# transmisorPCB_2_1.net
KiCad netlist of a schematic drawn in EAGLE
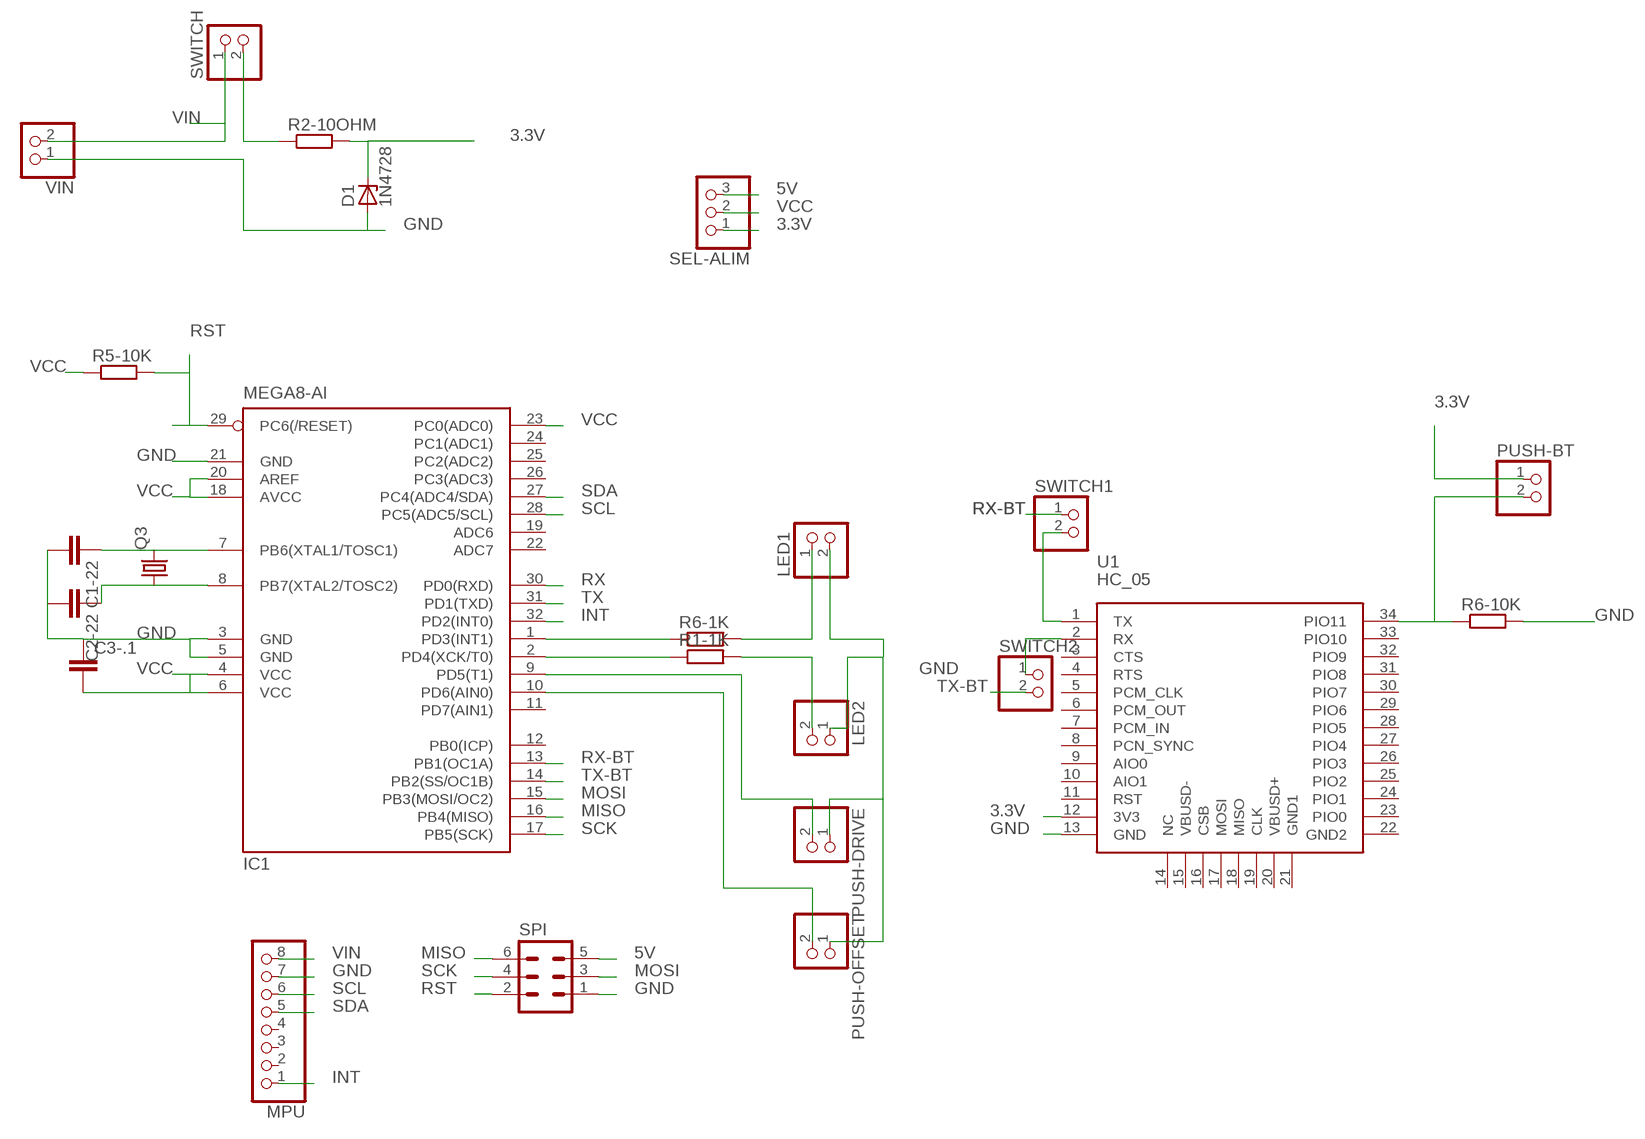
[diagram p0: schematic, sheet 1]

(export (version "E")
  (design (tool "Eeschema 10.0.6"))
  (components
    (comp (ref "C1-22")
      (value "C-EUC0402K")
      (footprint "eagle-import:C0402K")
      (libsource (lib "eagle-import") (part "C-EUC0402K"))
    )
    (comp (ref "C2-22")
      (value "C-EUC0402K")
      (footprint "eagle-import:C0402K")
      (libsource (lib "eagle-import") (part "C-EUC0402K"))
    )
    (comp (ref "C3-.1")
      (value "C-EUC0402K")
      (footprint "eagle-import:C0402K")
      (libsource (lib "eagle-import") (part "C-EUC0402K"))
    )
    (comp (ref "D1")
      (value "1N4728")
      (footprint "eagle-import:DO41Z10")
      (libsource (lib "eagle-import") (part "1N4728"))
    )
    (comp (ref "IC1")
      (value "MEGA8-AI")
      (footprint "eagle-import:TQFP32-08")
      (fields (field (name "MPN") "ATMEGA8-16AU"))
      (libsource (lib "eagle-import") (part "MEGA8-AI"))
    )
    (comp (ref "LED1")
      (value "PINHD-1X2")
      (footprint "eagle-import:1X02")
      (libsource (lib "eagle-import") (part "PINHD-1X2"))
    )
    (comp (ref "LED2")
      (value "PINHD-1X2")
      (footprint "eagle-import:1X02")
      (libsource (lib "eagle-import") (part "PINHD-1X2"))
    )
    (comp (ref "MPU")
      (value "PINHD-1X8")
      (footprint "eagle-import:1X08")
      (libsource (lib "eagle-import") (part "PINHD-1X8"))
    )
    (comp (ref "PUSH-BT")
      (value "PINHD-1X2")
      (footprint "eagle-import:1X02")
      (libsource (lib "eagle-import") (part "PINHD-1X2"))
    )
    (comp (ref "PUSH-DRIVE")
      (value "PINHD-1X2")
      (footprint "eagle-import:1X02")
      (libsource (lib "eagle-import") (part "PINHD-1X2"))
    )
    (comp (ref "PUSH-OFFSET")
      (value "PINHD-1X2")
      (footprint "eagle-import:1X02")
      (libsource (lib "eagle-import") (part "PINHD-1X2"))
    )
    (comp (ref "Q3")
      (value "CRYSTALHC49U70")
      (footprint "eagle-import:HC49U70")
      (libsource (lib "eagle-import") (part "CRYSTALHC49U70"))
    )
    (comp (ref "R1-1K")
      (value "R-EU_M1206")
      (footprint "eagle-import:M1206")
      (libsource (lib "eagle-import") (part "R-EU_M1206"))
    )
    (comp (ref "R2-10OHM")
      (value "R-EU_R2512")
      (footprint "eagle-import:R2512")
      (libsource (lib "eagle-import") (part "resistor_R-EU_R2512"))
    )
    (comp (ref "R5-10K")
      (value "R-EU_M1206")
      (footprint "eagle-import:M1206")
      (libsource (lib "eagle-import") (part "R-EU_M1206"))
    )
    (comp (ref "R6-1K")
      (value "R-EU_M1206")
      (footprint "eagle-import:M1206")
      (libsource (lib "eagle-import") (part "R-EU_M1206"))
    )
    (comp (ref "R6-10K")
      (value "R-EU_M1206")
      (footprint "eagle-import:M1206")
      (libsource (lib "eagle-import") (part "R-EU_M1206"))
    )
    (comp (ref "SEL-ALIM")
      (value "PINHD-1X3")
      (footprint "eagle-import:1X03")
      (libsource (lib "eagle-import") (part "PINHD-1X3"))
    )
    (comp (ref "SPI")
      (value "MA03-2")
      (footprint "eagle-import:MA03-2")
      (libsource (lib "eagle-import") (part "MA03-2"))
    )
    (comp (ref "SWITCH")
      (value "PINHD-1X2")
      (footprint "eagle-import:1X02")
      (libsource (lib "eagle-import") (part "PINHD-1X2"))
    )
    (comp (ref "SWITCH1")
      (value "PINHD-1X2")
      (footprint "eagle-import:1X02")
      (libsource (lib "eagle-import") (part "PINHD-1X2"))
    )
    (comp (ref "SWITCH2")
      (value "PINHD-1X2")
      (footprint "eagle-import:1X02")
      (libsource (lib "eagle-import") (part "PINHD-1X2"))
    )
    (comp (ref "U1")
      (value "HC_05")
      (footprint "eagle-import:BLUETOOTH_SMD")
      (libsource (lib "eagle-import") (part "HC_05"))
    )
    (comp (ref "VIN")
      (value "PINHD-1X2")
      (footprint "eagle-import:1X02")
      (libsource (lib "eagle-import") (part "PINHD-1X2"))
    )
  )
  (nets
    (net (code "1") (name "/3.3V") (class "Default")
      (node (ref "D1") (pin "C") (pinfunction "C_C") (pintype "passive"))
      (node (ref "PUSH-BT") (pin "1") (pinfunction "1_1") (pintype "passive"))
      (node (ref "R2-10OHM") (pin "2") (pinfunction "2_2") (pintype "passive"))
      (node (ref "SEL-ALIM") (pin "1") (pinfunction "1_1") (pintype "passive"))
      (node (ref "U1") (pin "12") (pinfunction "3V3_12") (pintype "bidirectional"))
    )
    (net (code "2") (name "/5V") (class "Default")
      (node (ref "SEL-ALIM") (pin "3") (pinfunction "3_3") (pintype "passive"))
      (node (ref "SPI") (pin "5") (pinfunction "5_5") (pintype "passive"))
    )
    (net (code "3") (name "/GND") (class "Default")
      (node (ref "C1-22") (pin "2") (pinfunction "2_2") (pintype "passive"))
      (node (ref "C2-22") (pin "2") (pinfunction "2_2") (pintype "passive"))
      (node (ref "C3-.1") (pin "1") (pinfunction "1_1") (pintype "passive"))
      (node (ref "D1") (pin "A") (pinfunction "A_A") (pintype "passive"))
      (node (ref "IC1") (pin "21") (pinfunction "GND_21") (pintype "power_in"))
      (node (ref "IC1") (pin "3") (pinfunction "GND_3") (pintype "power_in"))
      (node (ref "IC1") (pin "5") (pinfunction "GND_5") (pintype "power_in"))
      (node (ref "LED1") (pin "2") (pinfunction "2_2") (pintype "passive"))
      (node (ref "LED2") (pin "1") (pinfunction "1_1") (pintype "passive"))
      (node (ref "MPU") (pin "7") (pinfunction "7_7") (pintype "passive"))
      (node (ref "PUSH-DRIVE") (pin "1") (pinfunction "1_1") (pintype "passive"))
      (node (ref "PUSH-OFFSET") (pin "1") (pinfunction "1_1") (pintype "passive"))
      (node (ref "R6-10K") (pin "2") (pinfunction "2_2") (pintype "passive"))
      (node (ref "SPI") (pin "1") (pinfunction "1_1") (pintype "passive"))
      (node (ref "U1") (pin "13") (pinfunction "GND_13") (pintype "bidirectional"))
      (node (ref "VIN") (pin "1") (pinfunction "1_1") (pintype "passive"))
    )
    (net (code "4") (name "/INT") (class "Default")
      (node (ref "IC1") (pin "32") (pinfunction "PD2(INT0)_32") (pintype "bidirectional"))
      (node (ref "MPU") (pin "1") (pinfunction "1_1") (pintype "passive"))
    )
    (net (code "5") (name "/MISO") (class "Default")
      (node (ref "IC1") (pin "16") (pinfunction "PB4(MISO)_16") (pintype "bidirectional"))
      (node (ref "SPI") (pin "6") (pinfunction "6_6") (pintype "passive"))
    )
    (net (code "6") (name "/MOSI") (class "Default")
      (node (ref "IC1") (pin "15") (pinfunction "PB3(MOSI/OC2)_15") (pintype "bidirectional"))
      (node (ref "SPI") (pin "3") (pinfunction "3_3") (pintype "passive"))
    )
    (net (code "7") (name "/RST") (class "Default")
      (node (ref "IC1") (pin "29") (pinfunction "PC6(/RESET)_29") (pintype "bidirectional"))
      (node (ref "R5-10K") (pin "2") (pinfunction "2_2") (pintype "passive"))
      (node (ref "SPI") (pin "2") (pinfunction "2_2") (pintype "passive"))
    )
    (net (code "8") (name "/RX") (class "Default")
      (node (ref "IC1") (pin "30") (pinfunction "PD0(RXD)_30") (pintype "bidirectional"))
    )
    (net (code "9") (name "/RX-BT") (class "Default")
      (node (ref "IC1") (pin "13") (pinfunction "PB1(OC1A)_13") (pintype "bidirectional"))
      (node (ref "SWITCH1") (pin "1") (pinfunction "1_1") (pintype "passive"))
    )
    (net (code "10") (name "/SCK") (class "Default")
      (node (ref "IC1") (pin "17") (pinfunction "PB5(SCK)_17") (pintype "bidirectional"))
      (node (ref "SPI") (pin "4") (pinfunction "4_4") (pintype "passive"))
    )
    (net (code "11") (name "/SCL") (class "Default")
      (node (ref "IC1") (pin "28") (pinfunction "PC5(ADC5/SCL)_28") (pintype "bidirectional"))
      (node (ref "MPU") (pin "6") (pinfunction "6_6") (pintype "passive"))
    )
    (net (code "12") (name "/SDA") (class "Default")
      (node (ref "IC1") (pin "27") (pinfunction "PC4(ADC4/SDA)_27") (pintype "bidirectional"))
      (node (ref "MPU") (pin "5") (pinfunction "5_5") (pintype "passive"))
    )
    (net (code "13") (name "/TX") (class "Default")
      (node (ref "IC1") (pin "31") (pinfunction "PD1(TXD)_31") (pintype "bidirectional"))
    )
    (net (code "14") (name "/TX-BT") (class "Default")
      (node (ref "IC1") (pin "14") (pinfunction "PB2(SS/OC1B)_14") (pintype "bidirectional"))
      (node (ref "SWITCH2") (pin "2") (pinfunction "2_2") (pintype "passive"))
    )
    (net (code "15") (name "/VCC") (class "Default")
      (node (ref "C3-.1") (pin "2") (pinfunction "2_2") (pintype "passive"))
      (node (ref "IC1") (pin "18") (pinfunction "AVCC_18") (pintype "power_in"))
      (node (ref "IC1") (pin "20") (pinfunction "AREF_20") (pintype "passive"))
      (node (ref "IC1") (pin "23") (pinfunction "PC0(ADC0)_23") (pintype "bidirectional"))
      (node (ref "IC1") (pin "4") (pinfunction "VCC_4") (pintype "power_in"))
      (node (ref "IC1") (pin "6") (pinfunction "VCC_6") (pintype "power_in"))
      (node (ref "R5-10K") (pin "1") (pinfunction "1_1") (pintype "passive"))
      (node (ref "SEL-ALIM") (pin "2") (pinfunction "2_2") (pintype "passive"))
    )
    (net (code "16") (name "/VIN") (class "Default")
      (node (ref "MPU") (pin "8") (pinfunction "8_8") (pintype "passive"))
      (node (ref "SWITCH") (pin "1") (pinfunction "1_1") (pintype "passive"))
      (node (ref "VIN") (pin "2") (pinfunction "2_2") (pintype "passive"))
    )
    (net (code "17") (name "Net-(IC1-PB6(XTAL1{slash}TOSC1))") (class "Default")
      (node (ref "C1-22") (pin "1") (pinfunction "1_1") (pintype "passive"))
      (node (ref "IC1") (pin "7") (pinfunction "PB6(XTAL1/TOSC1)_7") (pintype "bidirectional"))
      (node (ref "Q3") (pin "2") (pinfunction "2_2") (pintype "passive"))
    )
    (net (code "18") (name "Net-(IC1-PB7(XTAL2{slash}TOSC2))") (class "Default")
      (node (ref "C2-22") (pin "1") (pinfunction "1_1") (pintype "passive"))
      (node (ref "IC1") (pin "8") (pinfunction "PB7(XTAL2/TOSC2)_8") (pintype "bidirectional"))
      (node (ref "Q3") (pin "1") (pinfunction "1_1") (pintype "passive"))
    )
    (net (code "19") (name "Net-(IC1-PD3(INT1))") (class "Default")
      (node (ref "IC1") (pin "1") (pinfunction "PD3(INT1)_1") (pintype "bidirectional"))
      (node (ref "R6-1K") (pin "1") (pinfunction "1_1") (pintype "passive"))
    )
    (net (code "20") (name "Net-(IC1-PD4(XCK{slash}T0))") (class "Default")
      (node (ref "IC1") (pin "2") (pinfunction "PD4(XCK/T0)_2") (pintype "bidirectional"))
      (node (ref "R1-1K") (pin "1") (pinfunction "1_1") (pintype "passive"))
    )
    (net (code "21") (name "Net-(IC1-PD5(T1))") (class "Default")
      (node (ref "IC1") (pin "9") (pinfunction "PD5(T1)_9") (pintype "bidirectional"))
      (node (ref "PUSH-DRIVE") (pin "2") (pinfunction "2_2") (pintype "passive"))
    )
    (net (code "22") (name "Net-(IC1-PD6(AIN0))") (class "Default")
      (node (ref "IC1") (pin "10") (pinfunction "PD6(AIN0)_10") (pintype "bidirectional"))
      (node (ref "PUSH-OFFSET") (pin "2") (pinfunction "2_2") (pintype "passive"))
    )
    (net (code "23") (name "Net-(LED1-Pad1)") (class "Default")
      (node (ref "LED1") (pin "1") (pinfunction "1_1") (pintype "passive"))
      (node (ref "R6-1K") (pin "2") (pinfunction "2_2") (pintype "passive"))
    )
    (net (code "24") (name "Net-(LED2-Pad2)") (class "Default")
      (node (ref "LED2") (pin "2") (pinfunction "2_2") (pintype "passive"))
      (node (ref "R1-1K") (pin "2") (pinfunction "2_2") (pintype "passive"))
    )
    (net (code "25") (name "Net-(R2-10OHM-Pad1)") (class "Default")
      (node (ref "R2-10OHM") (pin "1") (pinfunction "1_1") (pintype "passive"))
      (node (ref "SWITCH") (pin "2") (pinfunction "2_2") (pintype "passive"))
    )
    (net (code "26") (name "Net-(U1-PIO11)") (class "Default")
      (node (ref "PUSH-BT") (pin "2") (pinfunction "2_2") (pintype "passive"))
      (node (ref "R6-10K") (pin "1") (pinfunction "1_1") (pintype "passive"))
      (node (ref "U1") (pin "34") (pinfunction "PIO11_34") (pintype "bidirectional"))
    )
    (net (code "27") (name "Net-(U1-RX)") (class "Default")
      (node (ref "SWITCH2") (pin "1") (pinfunction "1_1") (pintype "passive"))
      (node (ref "U1") (pin "2") (pinfunction "RX_2") (pintype "bidirectional"))
    )
    (net (code "28") (name "Net-(U1-TX)") (class "Default")
      (node (ref "SWITCH1") (pin "2") (pinfunction "2_2") (pintype "passive"))
      (node (ref "U1") (pin "1") (pinfunction "TX_1") (pintype "bidirectional"))
    )
    (net (code "29") (name "unconnected-(IC1-ADC6-Pad19)") (class "Default")
      (node (ref "IC1") (pin "19") (pinfunction "ADC6_19") (pintype "bidirectional"))
    )
    (net (code "30") (name "unconnected-(IC1-ADC7-Pad22)") (class "Default")
      (node (ref "IC1") (pin "22") (pinfunction "ADC7_22") (pintype "bidirectional"))
    )
    (net (code "31") (name "unconnected-(IC1-PB0(ICP)-Pad12)") (class "Default")
      (node (ref "IC1") (pin "12") (pinfunction "PB0(ICP)_12") (pintype "bidirectional"))
    )
    (net (code "32") (name "unconnected-(IC1-PC1(ADC1)-Pad24)") (class "Default")
      (node (ref "IC1") (pin "24") (pinfunction "PC1(ADC1)_24") (pintype "bidirectional"))
    )
    (net (code "33") (name "unconnected-(IC1-PC2(ADC2)-Pad25)") (class "Default")
      (node (ref "IC1") (pin "25") (pinfunction "PC2(ADC2)_25") (pintype "bidirectional"))
    )
    (net (code "34") (name "unconnected-(IC1-PC3(ADC3)-Pad26)") (class "Default")
      (node (ref "IC1") (pin "26") (pinfunction "PC3(ADC3)_26") (pintype "bidirectional"))
    )
    (net (code "35") (name "unconnected-(IC1-PD7(AIN1)-Pad11)") (class "Default")
      (node (ref "IC1") (pin "11") (pinfunction "PD7(AIN1)_11") (pintype "bidirectional"))
    )
    (net (code "36") (name "unconnected-(MPU-Pad2)") (class "Default")
      (node (ref "MPU") (pin "2") (pinfunction "2_2") (pintype "passive"))
    )
    (net (code "37") (name "unconnected-(MPU-Pad3)") (class "Default")
      (node (ref "MPU") (pin "3") (pinfunction "3_3") (pintype "passive"))
    )
    (net (code "38") (name "unconnected-(MPU-Pad4)") (class "Default")
      (node (ref "MPU") (pin "4") (pinfunction "4_4") (pintype "passive"))
    )
    (net (code "39") (name "unconnected-(U1-AIO0-Pad9)") (class "Default")
      (node (ref "U1") (pin "9") (pinfunction "AIO0_9") (pintype "bidirectional"))
    )
    (net (code "40") (name "unconnected-(U1-AIO1-Pad10)") (class "Default")
      (node (ref "U1") (pin "10") (pinfunction "AIO1_10") (pintype "bidirectional"))
    )
    (net (code "41") (name "unconnected-(U1-CLK-Pad19)") (class "Default")
      (node (ref "U1") (pin "19") (pinfunction "CLK_19") (pintype "bidirectional"))
    )
    (net (code "42") (name "unconnected-(U1-CSB-Pad16)") (class "Default")
      (node (ref "U1") (pin "16") (pinfunction "CSB_16") (pintype "bidirectional"))
    )
    (net (code "43") (name "unconnected-(U1-CTS-Pad3)") (class "Default")
      (node (ref "U1") (pin "3") (pinfunction "CTS_3") (pintype "bidirectional"))
    )
    (net (code "44") (name "unconnected-(U1-GND1-Pad21)") (class "Default")
      (node (ref "U1") (pin "21") (pinfunction "GND1_21") (pintype "bidirectional"))
    )
    (net (code "45") (name "unconnected-(U1-GND2-Pad22)") (class "Default")
      (node (ref "U1") (pin "22") (pinfunction "GND2_22") (pintype "bidirectional"))
    )
    (net (code "46") (name "unconnected-(U1-MISO-Pad18)") (class "Default")
      (node (ref "U1") (pin "18") (pinfunction "MISO_18") (pintype "bidirectional"))
    )
    (net (code "47") (name "unconnected-(U1-MOSI-Pad17)") (class "Default")
      (node (ref "U1") (pin "17") (pinfunction "MOSI_17") (pintype "bidirectional"))
    )
    (net (code "48") (name "unconnected-(U1-NC-Pad14)") (class "Default")
      (node (ref "U1") (pin "14") (pinfunction "NC_14") (pintype "bidirectional"))
    )
    (net (code "49") (name "unconnected-(U1-PCM_CLK-Pad5)") (class "Default")
      (node (ref "U1") (pin "5") (pinfunction "PCM_CLK_5") (pintype "bidirectional"))
    )
    (net (code "50") (name "unconnected-(U1-PCM_IN-Pad7)") (class "Default")
      (node (ref "U1") (pin "7") (pinfunction "PCM_IN_7") (pintype "bidirectional"))
    )
    (net (code "51") (name "unconnected-(U1-PCM_OUT-Pad6)") (class "Default")
      (node (ref "U1") (pin "6") (pinfunction "PCM_OUT_6") (pintype "bidirectional"))
    )
    (net (code "52") (name "unconnected-(U1-PCN_SYNC-Pad8)") (class "Default")
      (node (ref "U1") (pin "8") (pinfunction "PCN_SYNC_8") (pintype "bidirectional"))
    )
    (net (code "53") (name "unconnected-(U1-PIO0-Pad23)") (class "Default")
      (node (ref "U1") (pin "23") (pinfunction "PIO0_23") (pintype "bidirectional"))
    )
    (net (code "54") (name "unconnected-(U1-PIO1-Pad24)") (class "Default")
      (node (ref "U1") (pin "24") (pinfunction "PIO1_24") (pintype "bidirectional"))
    )
    (net (code "55") (name "unconnected-(U1-PIO2-Pad25)") (class "Default")
      (node (ref "U1") (pin "25") (pinfunction "PIO2_25") (pintype "bidirectional"))
    )
    (net (code "56") (name "unconnected-(U1-PIO3-Pad26)") (class "Default")
      (node (ref "U1") (pin "26") (pinfunction "PIO3_26") (pintype "bidirectional"))
    )
    (net (code "57") (name "unconnected-(U1-PIO4-Pad27)") (class "Default")
      (node (ref "U1") (pin "27") (pinfunction "PIO4_27") (pintype "bidirectional"))
    )
    (net (code "58") (name "unconnected-(U1-PIO5-Pad28)") (class "Default")
      (node (ref "U1") (pin "28") (pinfunction "PIO5_28") (pintype "bidirectional"))
    )
    (net (code "59") (name "unconnected-(U1-PIO6-Pad29)") (class "Default")
      (node (ref "U1") (pin "29") (pinfunction "PIO6_29") (pintype "bidirectional"))
    )
    (net (code "60") (name "unconnected-(U1-PIO7-Pad30)") (class "Default")
      (node (ref "U1") (pin "30") (pinfunction "PIO7_30") (pintype "bidirectional"))
    )
    (net (code "61") (name "unconnected-(U1-PIO8-Pad31)") (class "Default")
      (node (ref "U1") (pin "31") (pinfunction "PIO8_31") (pintype "bidirectional"))
    )
    (net (code "62") (name "unconnected-(U1-PIO9-Pad32)") (class "Default")
      (node (ref "U1") (pin "32") (pinfunction "PIO9_32") (pintype "bidirectional"))
    )
    (net (code "63") (name "unconnected-(U1-PIO10-Pad33)") (class "Default")
      (node (ref "U1") (pin "33") (pinfunction "PIO10_33") (pintype "bidirectional"))
    )
    (net (code "64") (name "unconnected-(U1-RST-Pad11)") (class "Default")
      (node (ref "U1") (pin "11") (pinfunction "RST_11") (pintype "bidirectional"))
    )
    (net (code "65") (name "unconnected-(U1-RTS-Pad4)") (class "Default")
      (node (ref "U1") (pin "4") (pinfunction "RTS_4") (pintype "bidirectional"))
    )
    (net (code "66") (name "unconnected-(U1-VBUSD+-Pad20)") (class "Default")
      (node (ref "U1") (pin "20") (pinfunction "VBUSD+_20") (pintype "bidirectional"))
    )
    (net (code "67") (name "unconnected-(U1-VBUSD--Pad15)") (class "Default")
      (node (ref "U1") (pin "15") (pinfunction "VBUSD-_15") (pintype "bidirectional"))
    )
  )
)
